# vco_max2606.net
KiCad netlist of a schematic drawn in Altium Designer
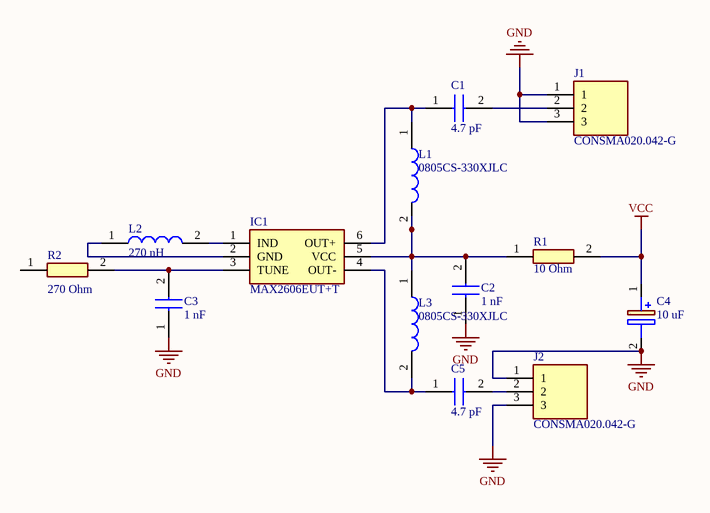
[diagram p0: vco_max2606.SchDoc]

(export (version "E")
  (design (tool "Eeschema 10.0.6"))
  (components
    (comp (ref "C1")
      (value "4.7 pF")
      (footprint "SamacSys:CAPC1608X90N")
      (description "Capacitor")
      (fields (field (name "MANUFACTURER_PART_NUMBER") "CL10C4R7BB8NNNC"))
      (libsource (lib "*") (part "CL10C4R7BB8NNNC"))
    )
    (comp (ref "C2")
      (value "1 nF")
      (footprint "SamacSys:CAPC1608X90N")
      (description "Capacitor")
      (fields
        (field (name "MANUFACTURER_PART_NUMBER") "06033D224MAT4A")
        (field (name "MOUSER PART NUMBER") "581-06033D224MAT4A")
      )
      (libsource (lib "SamacSys") (part "06033D224MAT4A"))
    )
    (comp (ref "C3")
      (value "1 nF")
      (footprint "SamacSys:CAPC1608X90N")
      (description "Capacitor")
      (fields
        (field (name "MANUFACTURER_PART_NUMBER") "06033D224MAT4A")
        (field (name "MOUSER PART NUMBER") "581-06033D224MAT4A")
      )
      (libsource (lib "SamacSys") (part "06033D224MAT4A"))
    )
    (comp (ref "C4")
      (value "10 uF")
      (footprint "SamacSys:CAPPM3216X180N")
      (description "Capacitor Polarised")
      (fields
        (field (name "MANUFACTURER_PART_NUMBER") "T491A106M010AT7454")
        (field (name "MOUSER PART NUMBER") "80-T491A106M10AT7454")
      )
      (libsource (lib "*") (part "T491A106M010AT7454"))
    )
    (comp (ref "C5")
      (value "4.7 pF")
      (footprint "SamacSys:CAPC1608X90N")
      (description "Capacitor")
      (fields (field (name "MANUFACTURER_PART_NUMBER") "CL10C4R7BB8NNNC"))
      (libsource (lib "*") (part "CL10C4R7BB8NNNC"))
    )
    (comp (ref "IC1")
      (value "MAX2606EUT+T")
      (footprint "SamacSys:SOT95P280X145-6N")
      (description "Integrated Circuit")
      (fields (field (name "MOUSER PART NUMBER") "700-MAX2606EUTT"))
      (libsource (lib "SamacSys") (part "MAX2606EUT+T"))
    )
    (comp (ref "J1")
      (value "CONSMA020.042-G")
      (footprint "SamacSys:CONSMA020042G")
      (description "Connector")
      (fields (field (name "MOUSER PART NUMBER") "712-CONSMA020.042-G"))
      (libsource (lib "SamacSys") (part "CONSMA020.042-G"))
    )
    (comp (ref "J2")
      (value "CONSMA020.042-G")
      (footprint "SamacSys:CONSMA020042G")
      (description "Connector")
      (fields (field (name "MOUSER PART NUMBER") "712-CONSMA020.042-G"))
      (libsource (lib "SamacSys") (part "CONSMA020.042-G"))
    )
    (comp (ref "L1")
      (value "0805CS-330XJLC")
      (footprint "CAPC2012X130N")
      (description "Inductor")
      (fields (field (name "MOUSER PART NUMBER") "994-0805CS-330XJLC"))
      (libsource (lib "*") (part "0805CS-330XJLC"))
    )
    (comp (ref "L2")
      (value "270 nH")
      (footprint "SamacSys:INDC2012X105N")
      (description "Inductor")
      (fields
        (field (name "MANUFACTURER_PART_NUMBER") "MLF2012DR27JTD25")
        (field (name "MOUSER PART NUMBER") "810-MLF2012DR27JTD25")
      )
      (libsource (lib "*") (part "MLF2012DR27JTD25"))
    )
    (comp (ref "L3")
      (value "0805CS-330XJLC")
      (footprint "CAPC2012X130N")
      (description "Inductor")
      (fields (field (name "MOUSER PART NUMBER") "994-0805CS-330XJLC"))
      (libsource (lib "*") (part "0805CS-330XJLC"))
    )
    (comp (ref "R1")
      (value "10 Ohm")
      (footprint "SamacSys:RESC1608X55N")
      (description "Resistor")
      (fields
        (field (name "MANUFACTURER_PART_NUMBER") "RT0603FRD0710RL")
        (field (name "MOUSER PART NUMBER") "603-RT0603FRD0710RL")
      )
      (libsource (lib "*") (part "RT0603FRD0710RL"))
    )
    (comp (ref "R2")
      (value "270 Ohm")
      (footprint "SamacSys:RESC2012X65N")
      (description "Resistor")
      (fields
        (field (name "MANUFACTURER_PART_NUMBER") "PCF0805R-3K24BT1")
        (field (name "MOUSER PART NUMBER") "756-PCF0805R3K24BT1")
      )
      (libsource (lib "SamacSys") (part "PCF0805R-3K24BT1"))
    )
  )
  (nets
    (net (code "1") (name "GND") (class "Default")
      (node (ref "C2") (pin "1") (pinfunction "1_1") (pintype "passive"))
      (node (ref "C3") (pin "1") (pinfunction "1_1") (pintype "passive"))
      (node (ref "C4") (pin "2") (pinfunction "-_2") (pintype "passive"))
      (node (ref "J1") (pin "1") (pinfunction "1_1") (pintype "passive"))
      (node (ref "J1") (pin "3") (pinfunction "3_3") (pintype "passive"))
      (node (ref "J2") (pin "1") (pinfunction "1_1") (pintype "passive"))
      (node (ref "J2") (pin "3") (pinfunction "3_3") (pintype "passive"))
    )
    (net (code "2") (name "Net-(C1-Pad2)") (class "Default")
      (node (ref "C1") (pin "2") (pinfunction "2_2") (pintype "passive"))
      (node (ref "J1") (pin "2") (pinfunction "2_2") (pintype "passive"))
    )
    (net (code "3") (name "Net-(C5-Pad2)") (class "Default")
      (node (ref "C5") (pin "2") (pinfunction "2_2") (pintype "passive"))
      (node (ref "J2") (pin "2") (pinfunction "2_2") (pintype "passive"))
    )
    (net (code "4") (name "Net-(IC1-GND)") (class "Default")
      (node (ref "IC1") (pin "2") (pinfunction "GND_2") (pintype "passive"))
      (node (ref "L2") (pin "1") (pinfunction "1_1") (pintype "passive"))
    )
    (net (code "5") (name "Net-(IC1-IND)") (class "Default")
      (node (ref "IC1") (pin "1") (pinfunction "IND_1") (pintype "passive"))
      (node (ref "L2") (pin "2") (pinfunction "2_2") (pintype "passive"))
    )
    (net (code "6") (name "Net-(IC1-OUT+)") (class "Default")
      (node (ref "C1") (pin "1") (pinfunction "1_1") (pintype "passive"))
      (node (ref "IC1") (pin "6") (pinfunction "OUT+_6") (pintype "passive"))
      (node (ref "L1") (pin "1") (pinfunction "1_1") (pintype "passive"))
    )
    (net (code "7") (name "Net-(IC1-OUT-)") (class "Default")
      (node (ref "C5") (pin "1") (pinfunction "1_1") (pintype "passive"))
      (node (ref "IC1") (pin "4") (pinfunction "OUT-_4") (pintype "passive"))
      (node (ref "L3") (pin "2") (pinfunction "2_2") (pintype "passive"))
    )
    (net (code "8") (name "Net-(IC1-TUNE)") (class "Default")
      (node (ref "C3") (pin "2") (pinfunction "2_2") (pintype "passive"))
      (node (ref "IC1") (pin "3") (pinfunction "TUNE_3") (pintype "passive"))
      (node (ref "R2") (pin "2") (pinfunction "2_2") (pintype "passive"))
    )
    (net (code "9") (name "Net-(IC1-VCC)") (class "Default")
      (node (ref "C2") (pin "2") (pinfunction "2_2") (pintype "passive"))
      (node (ref "IC1") (pin "5") (pinfunction "VCC_5") (pintype "passive"))
      (node (ref "L1") (pin "2") (pinfunction "2_2") (pintype "passive"))
      (node (ref "L3") (pin "1") (pinfunction "1_1") (pintype "passive"))
      (node (ref "R1") (pin "1") (pinfunction "1_1") (pintype "passive"))
    )
    (net (code "10") (name "VCC") (class "Default")
      (node (ref "C4") (pin "1") (pinfunction "+_1") (pintype "passive"))
      (node (ref "R1") (pin "2") (pinfunction "2_2") (pintype "passive"))
    )
    (net (code "11") (name "unconnected-(R2-Pad1)") (class "Default")
      (node (ref "R2") (pin "1") (pinfunction "1_1") (pintype "passive"))
    )
  )
)
